# LIA.net
KiCad netlist of a schematic drawn in Altium Designer
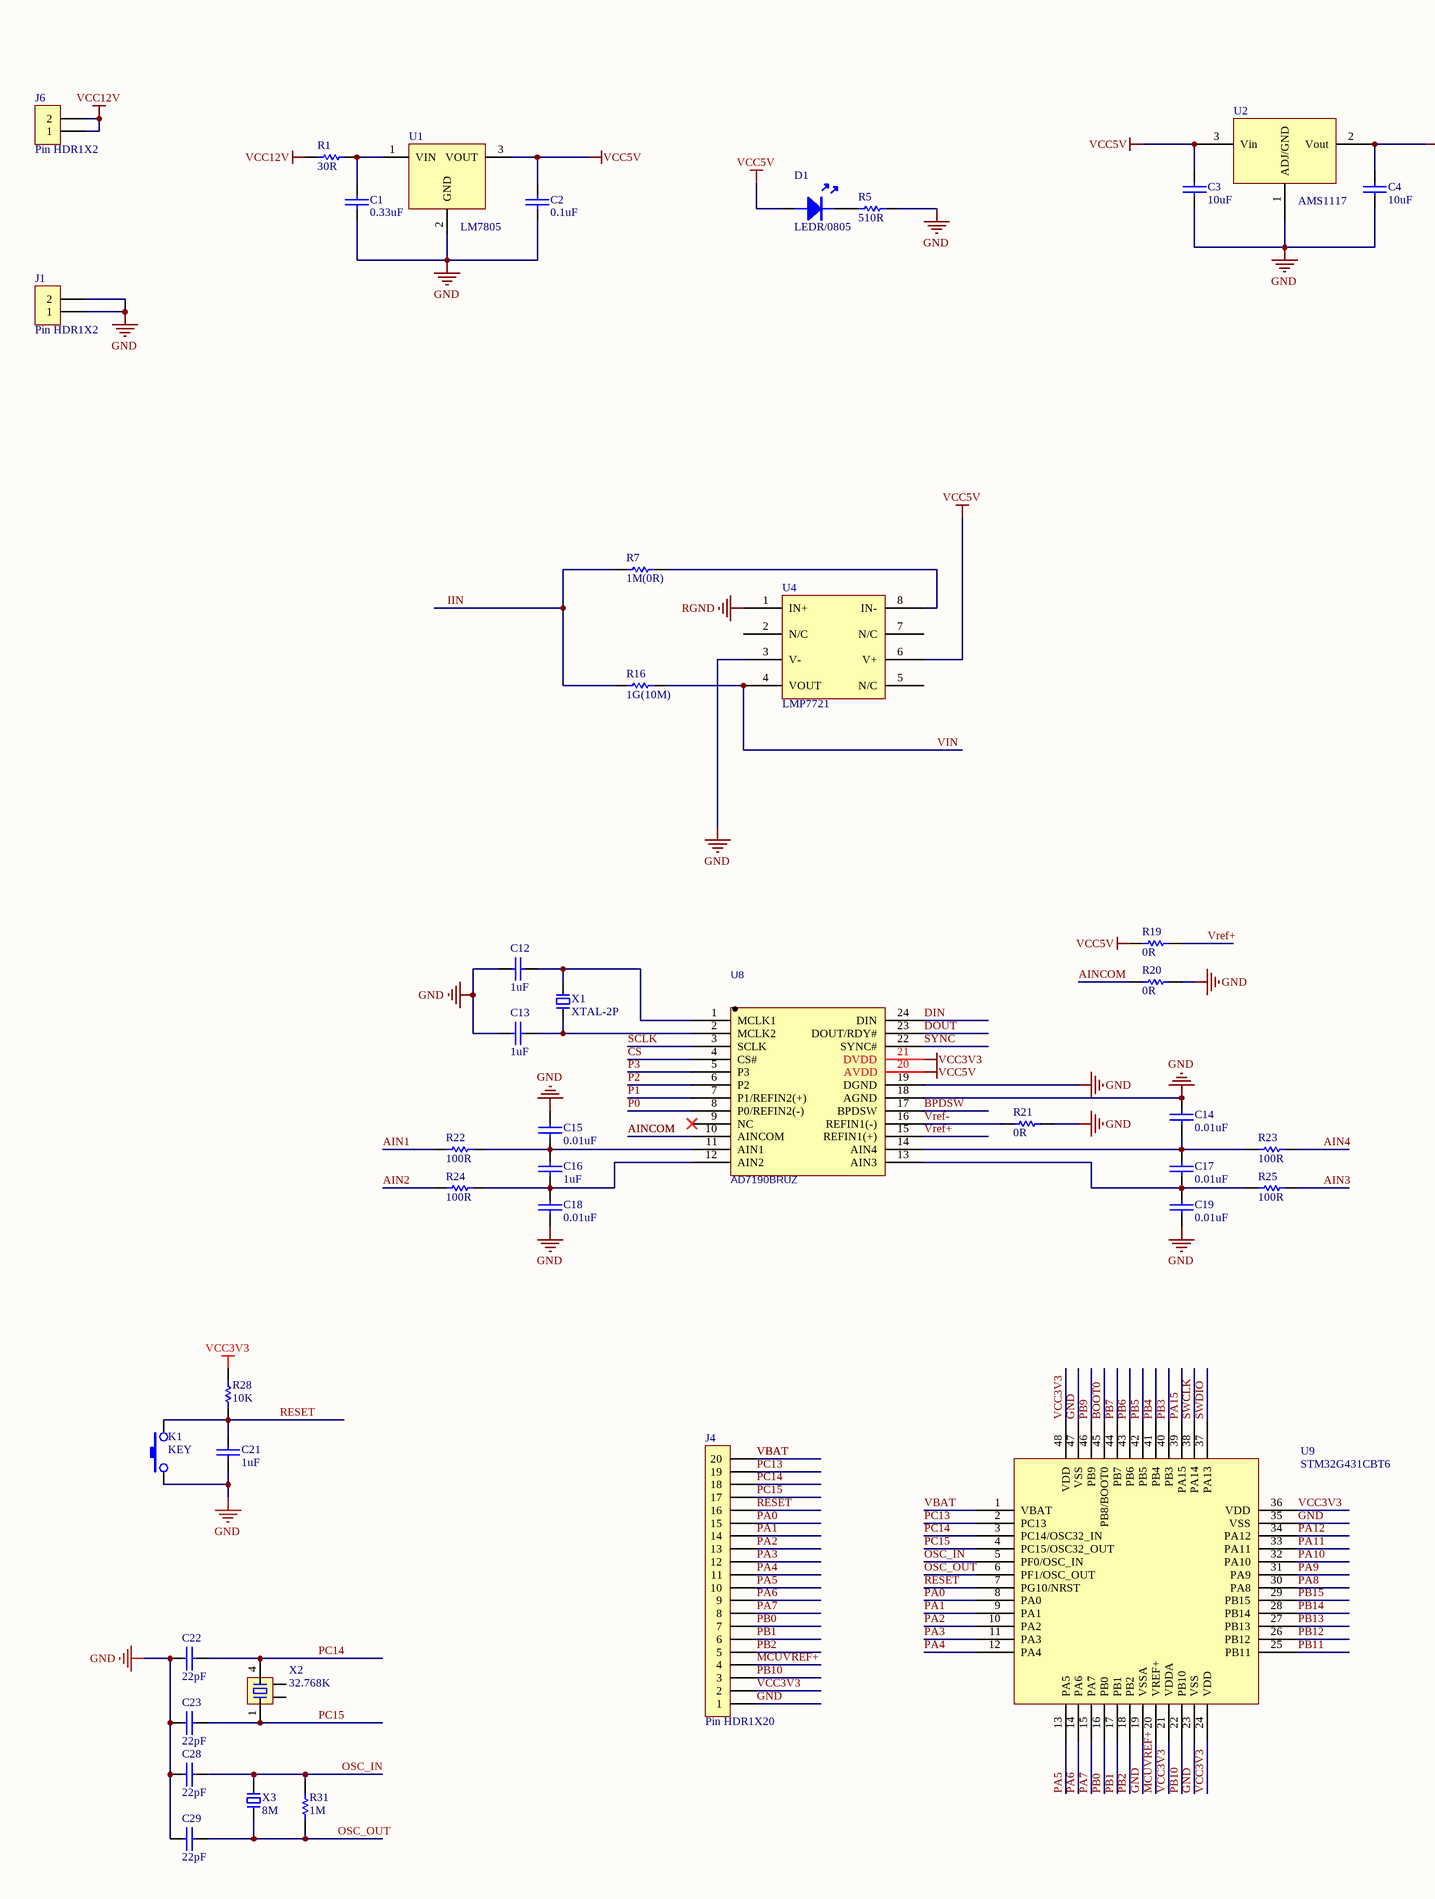
[diagram p0: LIA.SchDoc, left]
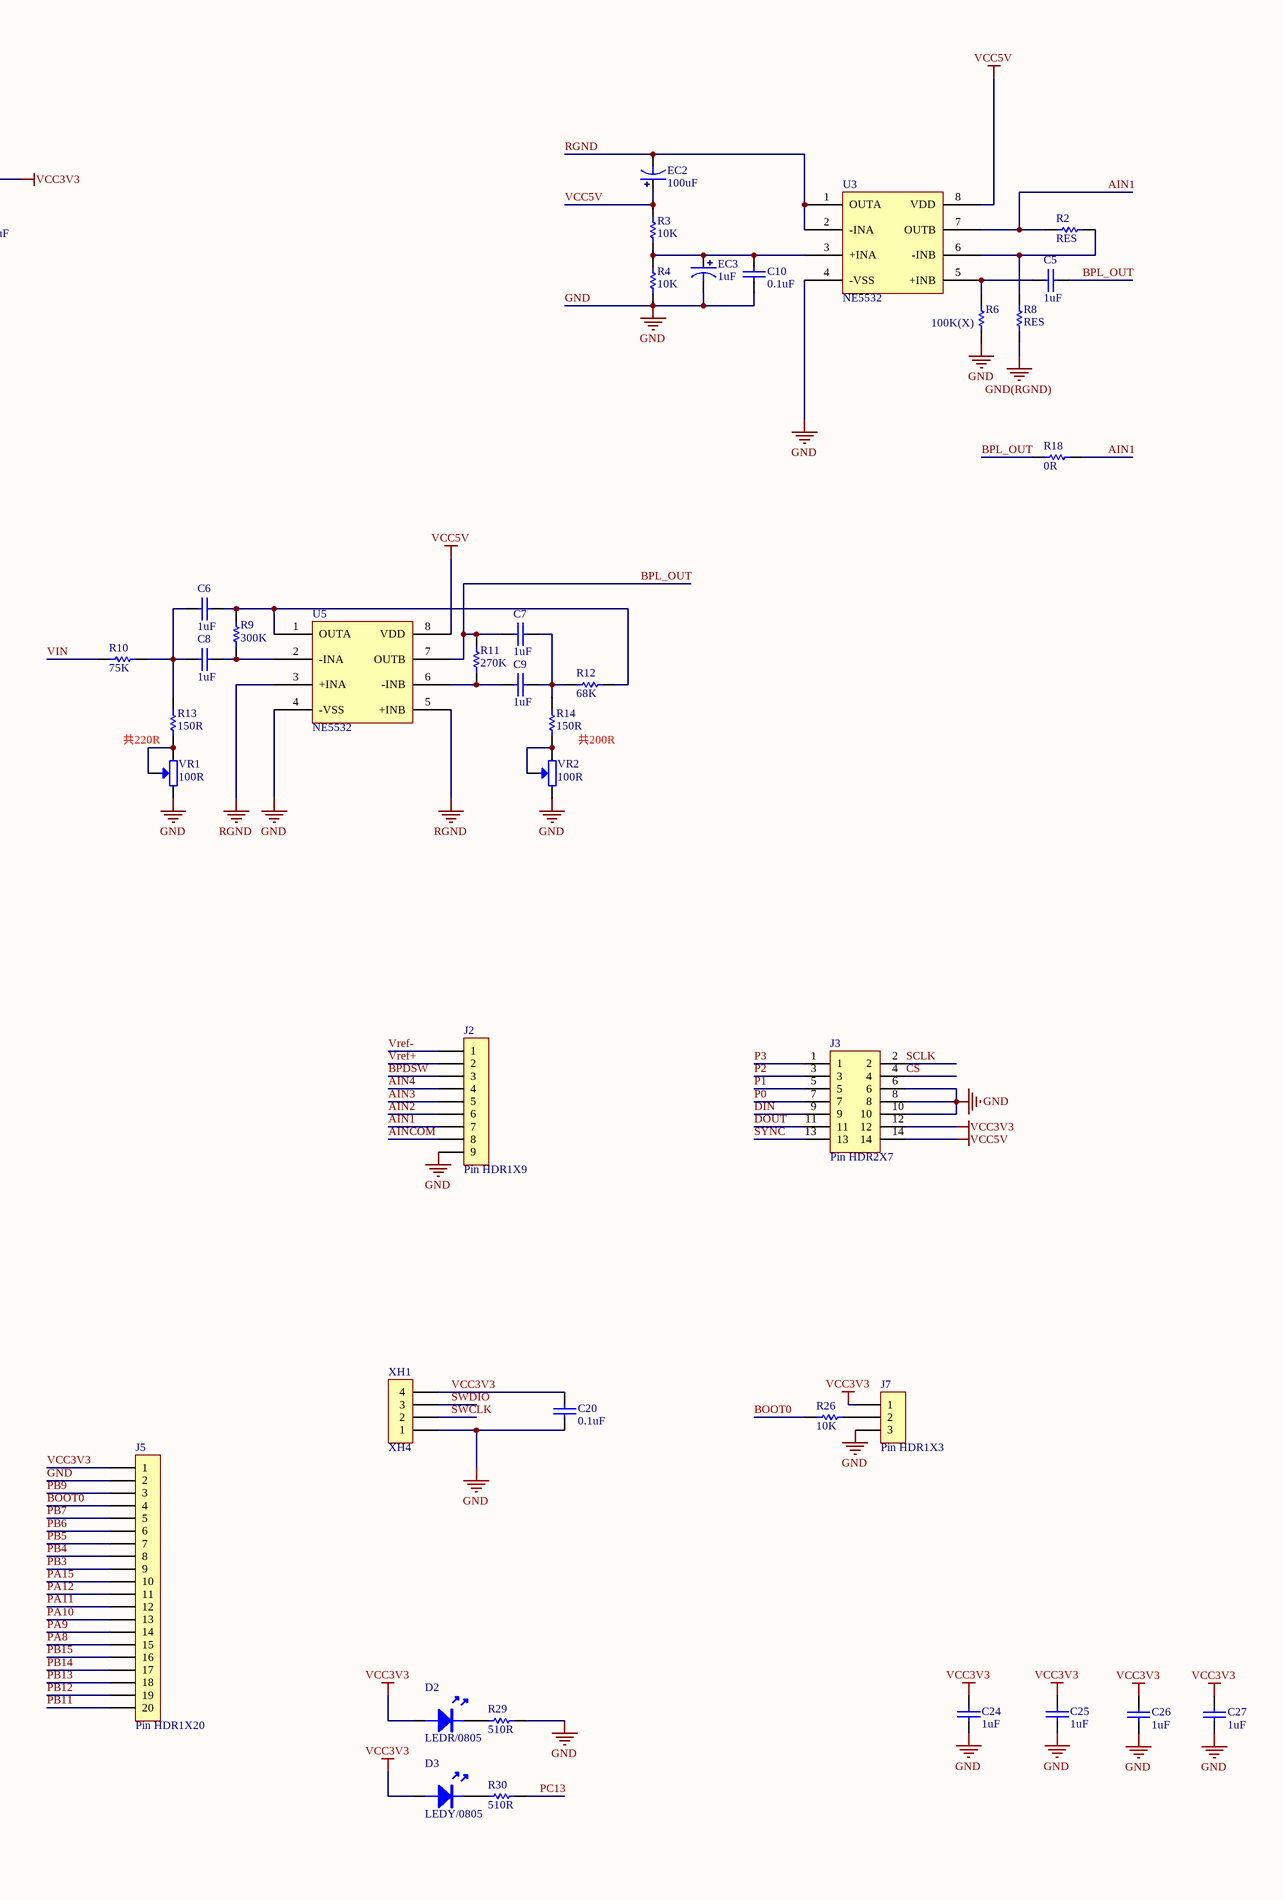
[diagram p1: LIA.SchDoc, right]

(export (version "E")
  (design (tool "Eeschema 10.0.6"))
  (components
    (comp (ref "C1")
      (value "0.33uF")
      (footprint "0603C")
      (description "无极性电容")
      (libsource (lib "电容") (part "CAP"))
    )
    (comp (ref "C2")
      (value "0.1uF")
      (footprint "0603C")
      (description "无极性电容")
      (libsource (lib "电容") (part "CAP"))
    )
    (comp (ref "C3")
      (value "10uF")
      (footprint "0603C")
      (description "无极性电容")
      (libsource (lib "电容") (part "CAP"))
    )
    (comp (ref "C4")
      (value "10uF")
      (footprint "0603C")
      (description "无极性电容")
      (libsource (lib "电容") (part "CAP"))
    )
    (comp (ref "C5")
      (value "1uF")
      (footprint "0603C")
      (description "无极性电容")
      (libsource (lib "电容") (part "CAP"))
    )
    (comp (ref "C6")
      (value "1uF")
      (footprint "DIP-7")
      (description "无极性电容")
      (libsource (lib "电容") (part "CAP"))
    )
    (comp (ref "C7")
      (value "1uF")
      (footprint "DIP-7")
      (description "无极性电容")
      (libsource (lib "电容") (part "CAP"))
    )
    (comp (ref "C8")
      (value "1uF")
      (footprint "DIP-7")
      (description "无极性电容")
      (libsource (lib "电容") (part "CAP"))
    )
    (comp (ref "C9")
      (value "1uF")
      (footprint "DIP-7")
      (description "无极性电容")
      (libsource (lib "电容") (part "CAP"))
    )
    (comp (ref "C10")
      (value "0.1uF")
      (footprint "0603C")
      (description "无极性电容")
      (libsource (lib "电容") (part "CAP"))
    )
    (comp (ref "C12")
      (value "1uF")
      (footprint "0603C")
      (description "无极性电容")
      (libsource (lib "电容") (part "CAP"))
    )
    (comp (ref "C13")
      (value "1uF")
      (footprint "0603C")
      (description "无极性电容")
      (libsource (lib "电容") (part "CAP"))
    )
    (comp (ref "C14")
      (value "0.01uF")
      (footprint "0603C")
      (description "无极性电容")
      (libsource (lib "电容") (part "CAP"))
    )
    (comp (ref "C15")
      (value "0.01uF")
      (footprint "0603C")
      (description "无极性电容")
      (libsource (lib "电容") (part "CAP"))
    )
    (comp (ref "C16")
      (value "1uF")
      (footprint "0603C")
      (description "无极性电容")
      (libsource (lib "电容") (part "CAP"))
    )
    (comp (ref "C17")
      (value "0.01uF")
      (footprint "0603C")
      (description "无极性电容")
      (libsource (lib "电容") (part "CAP"))
    )
    (comp (ref "C18")
      (value "0.01uF")
      (footprint "0603C")
      (description "无极性电容")
      (libsource (lib "电容") (part "CAP"))
    )
    (comp (ref "C19")
      (value "0.01uF")
      (footprint "0603C")
      (description "无极性电容")
      (libsource (lib "电容") (part "CAP"))
    )
    (comp (ref "C20")
      (value "0.1uF")
      (footprint "0603C")
      (description "无极性电容")
      (libsource (lib "电容") (part "CAP"))
    )
    (comp (ref "C21")
      (value "1uF")
      (footprint "0603C")
      (description "无极性电容")
      (libsource (lib "电容") (part "CAP"))
    )
    (comp (ref "C22")
      (value "22pF")
      (footprint "0603C")
      (description "无极性电容")
      (libsource (lib "电容") (part "CAP"))
    )
    (comp (ref "C23")
      (value "22pF")
      (footprint "0603C")
      (description "无极性电容")
      (libsource (lib "电容") (part "CAP"))
    )
    (comp (ref "C24")
      (value "1uF")
      (footprint "0603C")
      (description "无极性电容")
      (libsource (lib "电容") (part "CAP"))
    )
    (comp (ref "C25")
      (value "1uF")
      (footprint "0603C")
      (description "无极性电容")
      (libsource (lib "电容") (part "CAP"))
    )
    (comp (ref "C26")
      (value "1uF")
      (footprint "0603C")
      (description "无极性电容")
      (libsource (lib "电容") (part "CAP"))
    )
    (comp (ref "C27")
      (value "1uF")
      (footprint "0603C")
      (description "无极性电容")
      (libsource (lib "电容") (part "CAP"))
    )
    (comp (ref "C28")
      (value "22pF")
      (footprint "0603C")
      (description "无极性电容")
      (libsource (lib "电容") (part "CAP"))
    )
    (comp (ref "C29")
      (value "22pF")
      (footprint "0603C")
      (description "无极性电容")
      (libsource (lib "电容") (part "CAP"))
    )
    (comp (ref "D1") (value "LEDR/0805") (footprint "LED-0805R") (libsource (lib "LED") (part "LED")))
    (comp (ref "D2") (value "LEDR/0805") (footprint "LED-0805R") (libsource (lib "LED") (part "LED")))
    (comp (ref "D3") (value "LEDY/0805") (footprint "LED-0805Y") (libsource (lib "LED") (part "LED")))
    (comp (ref "EC2")
      (value "100uF")
      (footprint "SMD-EC6.3X6.3X10")
      (description "贴片电解电容")
      (libsource (lib "电容") (part "SMD_ECAP"))
    )
    (comp (ref "EC3")
      (value "1uF")
      (footprint "SMD-EC4.0X4.3X5.4")
      (description "贴片电解电容")
      (libsource (lib "电容") (part "SMD_ECAP"))
    )
    (comp (ref "J1")
      (value "Pin HDR1X2")
      (footprint "Pin HDR1X2/2.54mm-S")
      (libsource (lib "排针") (part "Pin HDR1X2"))
    )
    (comp (ref "J2")
      (value "Pin HDR1X9")
      (footprint "Pin HDR1X9/2.54mm-S")
      (libsource (lib "排针") (part "Pin HDR1X9"))
    )
    (comp (ref "J3")
      (value "Pin HDR2X7")
      (footprint "Pin HDR2X7/2.54mm-S")
      (libsource (lib "排针") (part "Pin HDR2X7"))
    )
    (comp (ref "J4")
      (value "Pin HDR1X20")
      (footprint "Pin HDR1X20/2.54mm-S")
      (libsource (lib "排针") (part "Pin HDR1X20"))
    )
    (comp (ref "J5")
      (value "Pin HDR1X20")
      (footprint "Pin HDR1X20/2.54mm-S")
      (libsource (lib "") (part "Pin HDR1X20_1"))
    )
    (comp (ref "J6")
      (value "Pin HDR1X2")
      (footprint "Pin HDR1X2/2.54mm-S")
      (libsource (lib "排针") (part "Pin HDR1X2"))
    )
    (comp (ref "J7")
      (value "Pin HDR1X3")
      (footprint "Pin HDR1X3/2.54mm-S")
      (libsource (lib "排针") (part "Pin HDR1X3"))
    )
    (comp (ref "K1") (value "KEY") (footprint "SMD-3X6X2.5") (libsource (lib "轻触开关") (part "KEY")))
    (comp (ref "R1") (value "30R") (footprint "0603R") (libsource (lib "电阻") (part "RES")))
    (comp (ref "R2") (value "RES") (footprint "0603R") (libsource (lib "电阻") (part "RES")))
    (comp (ref "R3") (value "10K") (footprint "0603R") (libsource (lib "电阻") (part "RES")))
    (comp (ref "R4") (value "10K") (footprint "0603R") (libsource (lib "电阻") (part "RES")))
    (comp (ref "R5") (value "510R") (footprint "0603R") (libsource (lib "电阻") (part "RES")))
    (comp (ref "R6") (value "100K(X)") (footprint "0603R") (libsource (lib "电阻") (part "RES")))
    (comp (ref "R7") (value "1M(0R)") (footprint "0603R") (libsource (lib "电阻") (part "RES")))
    (comp (ref "R8") (value "RES") (footprint "0603R") (libsource (lib "电阻") (part "RES")))
    (comp (ref "R9") (value "300K") (footprint "0603R") (libsource (lib "电阻") (part "RES")))
    (comp (ref "R10") (value "75K") (footprint "0603R") (libsource (lib "电阻") (part "RES")))
    (comp (ref "R11") (value "270K") (footprint "0603R") (libsource (lib "电阻") (part "RES")))
    (comp (ref "R12") (value "68K") (footprint "0603R") (libsource (lib "电阻") (part "RES")))
    (comp (ref "R13") (value "150R") (footprint "0603R") (libsource (lib "电阻") (part "RES")))
    (comp (ref "R14") (value "150R") (footprint "0603R") (libsource (lib "电阻") (part "RES")))
    (comp (ref "R16") (value "1G(10M)") (footprint "LONG") (libsource (lib "电阻") (part "RES")))
    (comp (ref "R18") (value "0R") (footprint "0603R") (libsource (lib "电阻") (part "RES")))
    (comp (ref "R19") (value "0R") (footprint "0603R") (libsource (lib "电阻") (part "RES")))
    (comp (ref "R20") (value "0R") (footprint "0603R") (libsource (lib "电阻") (part "RES")))
    (comp (ref "R21") (value "0R") (footprint "0603R") (libsource (lib "电阻") (part "RES")))
    (comp (ref "R22") (value "100R") (footprint "0603R") (libsource (lib "电阻") (part "RES")))
    (comp (ref "R23") (value "100R") (footprint "0603R") (libsource (lib "电阻") (part "RES")))
    (comp (ref "R24") (value "100R") (footprint "0603R") (libsource (lib "电阻") (part "RES")))
    (comp (ref "R25") (value "100R") (footprint "0603R") (libsource (lib "电阻") (part "RES")))
    (comp (ref "R26") (value "10K") (footprint "0603R") (libsource (lib "电阻") (part "RES")))
    (comp (ref "R28") (value "10K") (footprint "0603R") (libsource (lib "电阻") (part "RES")))
    (comp (ref "R29") (value "510R") (footprint "0603R") (libsource (lib "电阻") (part "RES")))
    (comp (ref "R30") (value "510R") (footprint "0603R") (libsource (lib "电阻") (part "RES")))
    (comp (ref "R31") (value "1M") (footprint "0603R") (libsource (lib "电阻") (part "RES")))
    (comp (ref "U1") (value "LM7805") (footprint "TO252") (libsource (lib "电源芯片") (part "LM7805")))
    (comp (ref "U2")
      (value "AMS1117")
      (footprint "SOT223")
      (description "三端稳压芯片")
      (libsource (lib "电源芯片") (part "AMS1117"))
    )
    (comp (ref "U3") (value "NE5532") (footprint "SOP8") (libsource (lib "未分类IC") (part "NE5532")))
    (comp (ref "U4") (value "LMP7721") (footprint "SOIC-8") (libsource (lib "未分类IC") (part "LMP7721")))
    (comp (ref "U5") (value "NE5532") (footprint "SOP8") (libsource (lib "未分类IC") (part "NE5532")))
    (comp (ref "U8")
      (value "AD7190BRUZ")
      (footprint "TSSOP24")
      (fields (field (name "BOM_SUPPLIER PART") "C578396") (field (name "CONTRIBUTOR") "LCSC"))
      (libsource (lib "未分类IC") (part "AD7190BRUZ"))
    )
    (comp (ref "U9")
      (value "STM32G431CBT6")
      (footprint "LQFP48 7X7")
      (libsource (lib "STM32系列") (part "STM32G431CBT6"))
    )
    (comp (ref "VR1") (value "100R") (footprint "3296W") (libsource (lib "电阻") (part "RESVR")))
    (comp (ref "VR2") (value "100R") (footprint "3296W") (libsource (lib "电阻") (part "RESVR")))
    (comp (ref "X1")
      (value "XTAL-2P")
      (footprint "OSC HC-49S")
      (description "2脚无源脚晶振")
      (libsource (lib "晶振") (part "XTAL-2P"))
    )
    (comp (ref "X2")
      (value "32.768K")
      (footprint "OSC MC-306")
      (description "MC系列4脚晶振")
      (libsource (lib "晶振") (part "XTAL-MC-4P"))
    )
    (comp (ref "X3")
      (value "8M")
      (footprint "OSC HC-49S")
      (description "2脚无源脚晶振")
      (libsource (lib "晶振") (part "XTAL-2P"))
    )
    (comp (ref "XH1") (value "XH4") (footprint "XH4/2.54mm/180") (libsource (lib "XH，VH") (part "XH4")))
  )
  (nets
    (net (code "1") (name "/AIN1") (class "Default")
      (node (ref "J2") (pin "7") (pinfunction "7_7") (pintype "passive"))
      (node (ref "R18") (pin "2") (pinfunction "2_2") (pintype "passive"))
      (node (ref "R2") (pin "1") (pinfunction "1_1") (pintype "passive"))
      (node (ref "R22") (pin "1") (pinfunction "1_1") (pintype "passive"))
      (node (ref "U3") (pin "7") (pinfunction "OUTB_7") (pintype "passive"))
    )
    (net (code "2") (name "/AIN2") (class "Default")
      (node (ref "J2") (pin "6") (pinfunction "6_6") (pintype "passive"))
      (node (ref "R24") (pin "1") (pinfunction "1_1") (pintype "passive"))
    )
    (net (code "3") (name "/AIN3") (class "Default")
      (node (ref "J2") (pin "5") (pinfunction "5_5") (pintype "passive"))
      (node (ref "R25") (pin "2") (pinfunction "2_2") (pintype "passive"))
    )
    (net (code "4") (name "/AIN4") (class "Default")
      (node (ref "J2") (pin "4") (pinfunction "4_4") (pintype "passive"))
      (node (ref "R23") (pin "2") (pinfunction "2_2") (pintype "passive"))
    )
    (net (code "5") (name "/AINCOM") (class "Default")
      (node (ref "J2") (pin "8") (pinfunction "8_8") (pintype "passive"))
      (node (ref "R20") (pin "1") (pinfunction "1_1") (pintype "passive"))
      (node (ref "U8") (pin "10") (pinfunction "AINCOM_10") (pintype "passive"))
    )
    (net (code "6") (name "/BOOT0") (class "Default")
      (node (ref "J5") (pin "4") (pinfunction "4_4") (pintype "passive"))
      (node (ref "R26") (pin "1") (pinfunction "1_1") (pintype "passive"))
      (node (ref "U9") (pin "45") (pinfunction "PB8/BOOT0_45") (pintype "passive"))
    )
    (net (code "7") (name "/BPDSW") (class "Default")
      (node (ref "J2") (pin "3") (pinfunction "3_3") (pintype "passive"))
      (node (ref "U8") (pin "17") (pinfunction "BPDSW_17") (pintype "passive"))
    )
    (net (code "8") (name "/BPL_OUT") (class "Default")
      (node (ref "C5") (pin "2") (pinfunction "2_2") (pintype "passive"))
      (node (ref "C7") (pin "2") (pinfunction "2_2") (pintype "passive"))
      (node (ref "R11") (pin "2") (pinfunction "2_2") (pintype "passive"))
      (node (ref "R18") (pin "1") (pinfunction "1_1") (pintype "passive"))
      (node (ref "U5") (pin "7") (pinfunction "OUTB_7") (pintype "passive"))
    )
    (net (code "9") (name "/CS") (class "Default")
      (node (ref "J3") (pin "4") (pinfunction "4_4") (pintype "passive"))
      (node (ref "U8") (pin "4") (pinfunction "CS#_4") (pintype "passive"))
    )
    (net (code "10") (name "/DIN") (class "Default")
      (node (ref "J3") (pin "9") (pinfunction "9_9") (pintype "passive"))
      (node (ref "U8") (pin "24") (pinfunction "DIN_24") (pintype "passive"))
    )
    (net (code "11") (name "/DOUT") (class "Default")
      (node (ref "J3") (pin "11") (pinfunction "11_11") (pintype "passive"))
      (node (ref "U8") (pin "23") (pinfunction "DOUT/RDY#_23") (pintype "passive"))
    )
    (net (code "12") (name "/IIN") (class "Default")
      (node (ref "R16") (pin "1") (pinfunction "1_1") (pintype "passive"))
      (node (ref "R7") (pin "2") (pinfunction "2_2") (pintype "passive"))
    )
    (net (code "13") (name "/MCUVREF+") (class "Default")
      (node (ref "J4") (pin "4") (pinfunction "4_4") (pintype "passive"))
      (node (ref "U9") (pin "20") (pinfunction "VREF+_20") (pintype "passive"))
    )
    (net (code "14") (name "/OSC_IN") (class "Default")
      (node (ref "C28") (pin "1") (pinfunction "1_1") (pintype "passive"))
      (node (ref "R31") (pin "2") (pinfunction "2_2") (pintype "passive"))
      (node (ref "U9") (pin "5") (pinfunction "PF0/OSC_IN_5") (pintype "passive"))
      (node (ref "X3") (pin "2") (pinfunction "2_2") (pintype "passive"))
    )
    (net (code "15") (name "/OSC_OUT") (class "Default")
      (node (ref "C29") (pin "1") (pinfunction "1_1") (pintype "passive"))
      (node (ref "R31") (pin "1") (pinfunction "1_1") (pintype "passive"))
      (node (ref "U9") (pin "6") (pinfunction "PF1/OSC_OUT_6") (pintype "passive"))
      (node (ref "X3") (pin "1") (pinfunction "1_1") (pintype "passive"))
    )
    (net (code "16") (name "/P0") (class "Default")
      (node (ref "J3") (pin "7") (pinfunction "7_7") (pintype "passive"))
      (node (ref "U8") (pin "8") (pinfunction "P0/REFIN2(-)_8") (pintype "passive"))
    )
    (net (code "17") (name "/P1") (class "Default")
      (node (ref "J3") (pin "5") (pinfunction "5_5") (pintype "passive"))
      (node (ref "U8") (pin "7") (pinfunction "P1/REFIN2(+)_7") (pintype "passive"))
    )
    (net (code "18") (name "/P2") (class "Default")
      (node (ref "J3") (pin "3") (pinfunction "3_3") (pintype "passive"))
      (node (ref "U8") (pin "6") (pinfunction "P2_6") (pintype "passive"))
    )
    (net (code "19") (name "/P3") (class "Default")
      (node (ref "J3") (pin "1") (pinfunction "1_1") (pintype "passive"))
      (node (ref "U8") (pin "5") (pinfunction "P3_5") (pintype "passive"))
    )
    (net (code "20") (name "/PA0") (class "Default")
      (node (ref "J4") (pin "15") (pinfunction "15_15") (pintype "passive"))
      (node (ref "U9") (pin "8") (pinfunction "PA0_8") (pintype "passive"))
    )
    (net (code "21") (name "/PA1") (class "Default")
      (node (ref "J4") (pin "14") (pinfunction "14_14") (pintype "passive"))
      (node (ref "U9") (pin "9") (pinfunction "PA1_9") (pintype "passive"))
    )
    (net (code "22") (name "/PA2") (class "Default")
      (node (ref "J4") (pin "13") (pinfunction "13_13") (pintype "passive"))
      (node (ref "U9") (pin "10") (pinfunction "PA2_10") (pintype "passive"))
    )
    (net (code "23") (name "/PA3") (class "Default")
      (node (ref "J4") (pin "12") (pinfunction "12_12") (pintype "passive"))
      (node (ref "U9") (pin "11") (pinfunction "PA3_11") (pintype "passive"))
    )
    (net (code "24") (name "/PA4") (class "Default")
      (node (ref "J4") (pin "11") (pinfunction "11_11") (pintype "passive"))
      (node (ref "U9") (pin "12") (pinfunction "PA4_12") (pintype "passive"))
    )
    (net (code "25") (name "/PA5") (class "Default")
      (node (ref "J4") (pin "10") (pinfunction "10_10") (pintype "passive"))
      (node (ref "U9") (pin "13") (pinfunction "PA5_13") (pintype "passive"))
    )
    (net (code "26") (name "/PA6") (class "Default")
      (node (ref "J4") (pin "9") (pinfunction "9_9") (pintype "passive"))
      (node (ref "U9") (pin "14") (pinfunction "PA6_14") (pintype "passive"))
    )
    (net (code "27") (name "/PA7") (class "Default")
      (node (ref "J4") (pin "8") (pinfunction "8_8") (pintype "passive"))
      (node (ref "U9") (pin "15") (pinfunction "PA7_15") (pintype "passive"))
    )
    (net (code "28") (name "/PA8") (class "Default")
      (node (ref "J5") (pin "15") (pinfunction "15_15") (pintype "passive"))
      (node (ref "U9") (pin "30") (pinfunction "PA8_30") (pintype "passive"))
    )
    (net (code "29") (name "/PA9") (class "Default")
      (node (ref "J5") (pin "14") (pinfunction "14_14") (pintype "passive"))
      (node (ref "U9") (pin "31") (pinfunction "PA9_31") (pintype "passive"))
    )
    (net (code "30") (name "/PA10") (class "Default")
      (node (ref "J5") (pin "13") (pinfunction "13_13") (pintype "passive"))
      (node (ref "U9") (pin "32") (pinfunction "PA10_32") (pintype "passive"))
    )
    (net (code "31") (name "/PA11") (class "Default")
      (node (ref "J5") (pin "12") (pinfunction "12_12") (pintype "passive"))
      (node (ref "U9") (pin "33") (pinfunction "PA11_33") (pintype "passive"))
    )
    (net (code "32") (name "/PA12") (class "Default")
      (node (ref "J5") (pin "11") (pinfunction "11_11") (pintype "passive"))
      (node (ref "U9") (pin "34") (pinfunction "PA12_34") (pintype "passive"))
    )
    (net (code "33") (name "/PA15") (class "Default")
      (node (ref "J5") (pin "10") (pinfunction "10_10") (pintype "passive"))
      (node (ref "U9") (pin "39") (pinfunction "PA15_39") (pintype "passive"))
    )
    (net (code "34") (name "/PB0") (class "Default")
      (node (ref "J4") (pin "7") (pinfunction "7_7") (pintype "passive"))
      (node (ref "U9") (pin "16") (pinfunction "PB0_16") (pintype "passive"))
    )
    (net (code "35") (name "/PB1") (class "Default")
      (node (ref "J4") (pin "6") (pinfunction "6_6") (pintype "passive"))
      (node (ref "U9") (pin "17") (pinfunction "PB1_17") (pintype "passive"))
    )
    (net (code "36") (name "/PB2") (class "Default")
      (node (ref "J4") (pin "5") (pinfunction "5_5") (pintype "passive"))
      (node (ref "U9") (pin "18") (pinfunction "PB2_18") (pintype "passive"))
    )
    (net (code "37") (name "/PB3") (class "Default")
      (node (ref "J5") (pin "9") (pinfunction "9_9") (pintype "passive"))
      (node (ref "U9") (pin "40") (pinfunction "PB3_40") (pintype "passive"))
    )
    (net (code "38") (name "/PB4") (class "Default")
      (node (ref "J5") (pin "8") (pinfunction "8_8") (pintype "passive"))
      (node (ref "U9") (pin "41") (pinfunction "PB4_41") (pintype "passive"))
    )
    (net (code "39") (name "/PB5") (class "Default")
      (node (ref "J5") (pin "7") (pinfunction "7_7") (pintype "passive"))
      (node (ref "U9") (pin "42") (pinfunction "PB5_42") (pintype "passive"))
    )
    (net (code "40") (name "/PB6") (class "Default")
      (node (ref "J5") (pin "6") (pinfunction "6_6") (pintype "passive"))
      (node (ref "U9") (pin "43") (pinfunction "PB6_43") (pintype "passive"))
    )
    (net (code "41") (name "/PB7") (class "Default")
      (node (ref "J5") (pin "5") (pinfunction "5_5") (pintype "passive"))
      (node (ref "U9") (pin "44") (pinfunction "PB7_44") (pintype "passive"))
    )
    (net (code "42") (name "/PB9") (class "Default")
      (node (ref "J5") (pin "3") (pinfunction "3_3") (pintype "passive"))
      (node (ref "U9") (pin "46") (pinfunction "PB9_46") (pintype "passive"))
    )
    (net (code "43") (name "/PB10") (class "Default")
      (node (ref "J4") (pin "3") (pinfunction "3_3") (pintype "passive"))
      (node (ref "U9") (pin "22") (pinfunction "PB10_22") (pintype "passive"))
    )
    (net (code "44") (name "/PB11") (class "Default")
      (node (ref "J5") (pin "20") (pinfunction "20_20") (pintype "passive"))
      (node (ref "U9") (pin "25") (pinfunction "PB11_25") (pintype "passive"))
    )
    (net (code "45") (name "/PB12") (class "Default")
      (node (ref "J5") (pin "19") (pinfunction "19_19") (pintype "passive"))
      (node (ref "U9") (pin "26") (pinfunction "PB12_26") (pintype "passive"))
    )
    (net (code "46") (name "/PB13") (class "Default")
      (node (ref "J5") (pin "18") (pinfunction "18_18") (pintype "passive"))
      (node (ref "U9") (pin "27") (pinfunction "PB13_27") (pintype "passive"))
    )
    (net (code "47") (name "/PB14") (class "Default")
      (node (ref "J5") (pin "17") (pinfunction "17_17") (pintype "passive"))
      (node (ref "U9") (pin "28") (pinfunction "PB14_28") (pintype "passive"))
    )
    (net (code "48") (name "/PB15") (class "Default")
      (node (ref "J5") (pin "16") (pinfunction "16_16") (pintype "passive"))
      (node (ref "U9") (pin "29") (pinfunction "PB15_29") (pintype "passive"))
    )
    (net (code "49") (name "/PC13") (class "Default")
      (node (ref "J4") (pin "19") (pinfunction "19_19") (pintype "passive"))
      (node (ref "R30") (pin "2") (pinfunction "2_2") (pintype "passive"))
      (node (ref "U9") (pin "2") (pinfunction "PC13_2") (pintype "passive"))
    )
    (net (code "50") (name "/PC14") (class "Default")
      (node (ref "C22") (pin "1") (pinfunction "1_1") (pintype "passive"))
      (node (ref "J4") (pin "18") (pinfunction "18_18") (pintype "passive"))
      (node (ref "U9") (pin "3") (pinfunction "PC14/OSC32_IN_3") (pintype "passive"))
      (node (ref "X2") (pin "4") (pinfunction "4_4") (pintype "passive"))
    )
    (net (code "51") (name "/PC15") (class "Default")
      (node (ref "C23") (pin "1") (pinfunction "1_1") (pintype "passive"))
      (node (ref "J4") (pin "17") (pinfunction "17_17") (pintype "passive"))
      (node (ref "U9") (pin "4") (pinfunction "PC15/OSC32_OUT_4") (pintype "passive"))
      (node (ref "X2") (pin "1") (pinfunction "1_1") (pintype "passive"))
    )
    (net (code "52") (name "/RESET") (class "Default")
      (node (ref "C21") (pin "2") (pinfunction "2_2") (pintype "passive"))
      (node (ref "J4") (pin "16") (pinfunction "16_16") (pintype "passive"))
      (node (ref "K1") (pin "3") (pinfunction "3_3") (pintype "passive"))
      (node (ref "R28") (pin "2") (pinfunction "2_2") (pintype "passive"))
      (node (ref "U9") (pin "7") (pinfunction "PG10/NRST_7") (pintype "passive"))
    )
    (net (code "53") (name "/SCLK") (class "Default")
      (node (ref "J3") (pin "2") (pinfunction "2_2") (pintype "passive"))
      (node (ref "U8") (pin "3") (pinfunction "SCLK_3") (pintype "passive"))
    )
    (net (code "54") (name "/SWCLK") (class "Default")
      (node (ref "U9") (pin "38") (pinfunction "PA14_38") (pintype "passive"))
      (node (ref "XH1") (pin "2") (pinfunction "2_2") (pintype "passive"))
    )
    (net (code "55") (name "/SWDIO") (class "Default")
      (node (ref "U9") (pin "37") (pinfunction "PA13_37") (pintype "passive"))
      (node (ref "XH1") (pin "3") (pinfunction "3_3") (pintype "passive"))
    )
    (net (code "56") (name "/SYNC") (class "Default")
      (node (ref "J3") (pin "13") (pinfunction "13_13") (pintype "passive"))
      (node (ref "U8") (pin "22") (pinfunction "SYNC#_22") (pintype "passive"))
    )
    (net (code "57") (name "/VBAT") (class "Default")
      (node (ref "J4") (pin "20") (pinfunction "20_20") (pintype "passive"))
      (node (ref "U9") (pin "1") (pinfunction "VBAT_1") (pintype "passive"))
    )
    (net (code "58") (name "/VIN") (class "Default")
      (node (ref "R10") (pin "2") (pinfunction "2_2") (pintype "passive"))
      (node (ref "R16") (pin "2") (pinfunction "2_2") (pintype "passive"))
      (node (ref "U4") (pin "4") (pinfunction "VOUT_4") (pintype "passive"))
    )
    (net (code "59") (name "/Vref+") (class "Default")
      (node (ref "J2") (pin "2") (pinfunction "2_2") (pintype "passive"))
      (node (ref "R19") (pin "2") (pinfunction "2_2") (pintype "passive"))
      (node (ref "U8") (pin "15") (pinfunction "REFIN1(+)_15") (pintype "passive"))
    )
    (net (code "60") (name "/Vref-") (class "Default")
      (node (ref "J2") (pin "1") (pinfunction "1_1") (pintype "passive"))
      (node (ref "R21") (pin "1") (pinfunction "1_1") (pintype "passive"))
      (node (ref "U8") (pin "16") (pinfunction "REFIN1(-)_16") (pintype "passive"))
    )
    (net (code "61") (name "GND") (class "Default")
      (node (ref "C1") (pin "1") (pinfunction "1_1") (pintype "passive"))
      (node (ref "C10") (pin "1") (pinfunction "1_1") (pintype "passive"))
      (node (ref "C12") (pin "2") (pinfunction "2_2") (pintype "passive"))
      (node (ref "C13") (pin "2") (pinfunction "2_2") (pintype "passive"))
      (node (ref "C14") (pin "2") (pinfunction "2_2") (pintype "passive"))
      (node (ref "C15") (pin "2") (pinfunction "2_2") (pintype "passive"))
      (node (ref "C18") (pin "1") (pinfunction "1_1") (pintype "passive"))
      (node (ref "C19") (pin "1") (pinfunction "1_1") (pintype "passive"))
      (node (ref "C2") (pin "1") (pinfunction "1_1") (pintype "passive"))
      (node (ref "C20") (pin "1") (pinfunction "1_1") (pintype "passive"))
      (node (ref "C21") (pin "1") (pinfunction "1_1") (pintype "passive"))
      (node (ref "C22") (pin "2") (pinfunction "2_2") (pintype "passive"))
      (node (ref "C23") (pin "2") (pinfunction "2_2") (pintype "passive"))
      (node (ref "C24") (pin "1") (pinfunction "1_1") (pintype "passive"))
      (node (ref "C25") (pin "1") (pinfunction "1_1") (pintype "passive"))
      (node (ref "C26") (pin "1") (pinfunction "1_1") (pintype "passive"))
      (node (ref "C27") (pin "1") (pinfunction "1_1") (pintype "passive"))
      (node (ref "C28") (pin "2") (pinfunction "2_2") (pintype "passive"))
      (node (ref "C29") (pin "2") (pinfunction "2_2") (pintype "passive"))
      (node (ref "C3") (pin "1") (pinfunction "1_1") (pintype "passive"))
      (node (ref "C4") (pin "1") (pinfunction "1_1") (pintype "passive"))
      (node (ref "EC3") (pin "2") (pinfunction "2_2") (pintype "passive"))
      (node (ref "J1") (pin "1") (pinfunction "1_1") (pintype "passive"))
      (node (ref "J1") (pin "2") (pinfunction "2_2") (pintype "passive"))
      (node (ref "J2") (pin "9") (pinfunction "9_9") (pintype "passive"))
      (node (ref "J3") (pin "10") (pinfunction "10_10") (pintype "passive"))
      (node (ref "J3") (pin "6") (pinfunction "6_6") (pintype "passive"))
      (node (ref "J3") (pin "8") (pinfunction "8_8") (pintype "passive"))
      (node (ref "J4") (pin "1") (pinfunction "1_1") (pintype "passive"))
      (node (ref "J5") (pin "2") (pinfunction "2_2") (pintype "passive"))
      (node (ref "J7") (pin "3") (pinfunction "3_3") (pintype "passive"))
      (node (ref "K1") (pin "1") (pinfunction "1_1") (pintype "passive"))
      (node (ref "R20") (pin "2") (pinfunction "2_2") (pintype "passive"))
      (node (ref "R21") (pin "2") (pinfunction "2_2") (pintype "passive"))
      (node (ref "R29") (pin "2") (pinfunction "2_2") (pintype "passive"))
      (node (ref "R4") (pin "2") (pinfunction "2_2") (pintype "passive"))
      (node (ref "R5") (pin "2") (pinfunction "2_2") (pintype "passive"))
      (node (ref "R6") (pin "1") (pinfunction "1_1") (pintype "passive"))
      (node (ref "U1") (pin "2") (pinfunction "GND_2") (pintype "passive"))
      (node (ref "U2") (pin "1") (pinfunction "ADJ/GND_1") (pintype "passive"))
      (node (ref "U3") (pin "4") (pinfunction "-VSS_4") (pintype "passive"))
      (node (ref "U4") (pin "3") (pinfunction "V-_3") (pintype "passive"))
      (node (ref "U5") (pin "4") (pinfunction "-VSS_4") (pintype "passive"))
      (node (ref "U8") (pin "18") (pinfunction "AGND_18") (pintype "passive"))
      (node (ref "U8") (pin "19") (pinfunction "DGND_19") (pintype "passive"))
      (node (ref "U9") (pin "19") (pinfunction "VSSA_19") (pintype "passive"))
      (node (ref "U9") (pin "23") (pinfunction "VSS_23") (pintype "passive"))
      (node (ref "U9") (pin "35") (pinfunction "VSS_35") (pintype "passive"))
      (node (ref "U9") (pin "47") (pinfunction "VSS_47") (pintype "passive"))
      (node (ref "VR1") (pin "1") (pinfunction "1_1") (pintype "passive"))
      (node (ref "VR2") (pin "1") (pinfunction "1_1") (pintype "passive"))
      (node (ref "XH1") (pin "1") (pinfunction "1_1") (pintype "passive"))
    )
    (net (code "62") (name "GND(RGND)") (class "Default")
      (node (ref "R8") (pin "2") (pinfunction "2_2") (pintype "passive"))
    )
    (net (code "63") (name "Net-(C6-Pad2)") (class "Default")
      (node (ref "C6") (pin "2") (pinfunction "2_2") (pintype "passive"))
      (node (ref "C8") (pin "1") (pinfunction "1_1") (pintype "passive"))
      (node (ref "R10") (pin "1") (pinfunction "1_1") (pintype "passive"))
      (node (ref "R13") (pin "1") (pinfunction "1_1") (pintype "passive"))
    )
    (net (code "64") (name "Net-(C7-Pad1)") (class "Default")
      (node (ref "C7") (pin "1") (pinfunction "1_1") (pintype "passive"))
      (node (ref "C9") (pin "2") (pinfunction "2_2") (pintype "passive"))
      (node (ref "R12") (pin "2") (pinfunction "2_2") (pintype "passive"))
      (node (ref "R14") (pin "1") (pinfunction "1_1") (pintype "passive"))
    )
    (net (code "65") (name "Net-(D1-PadK)") (class "Default")
      (node (ref "D1") (pin "K") (pinfunction "K_K") (pintype "passive"))
      (node (ref "R5") (pin "1") (pinfunction "1_1") (pintype "passive"))
    )
    (net (code "66") (name "Net-(D2-PadK)") (class "Default")
      (node (ref "D2") (pin "K") (pinfunction "K_K") (pintype "passive"))
      (node (ref "R29") (pin "1") (pinfunction "1_1") (pintype "passive"))
    )
    (net (code "67") (name "Net-(D3-PadK)") (class "Default")
      (node (ref "D3") (pin "K") (pinfunction "K_K") (pintype "passive"))
      (node (ref "R30") (pin "1") (pinfunction "1_1") (pintype "passive"))
    )
    (net (code "68") (name "Net-(J7-Pad2)") (class "Default")
      (node (ref "J7") (pin "2") (pinfunction "2_2") (pintype "passive"))
      (node (ref "R26") (pin "2") (pinfunction "2_2") (pintype "passive"))
    )
    (net (code "69") (name "Net-(R13-Pad2)") (class "Default")
      (node (ref "R13") (pin "2") (pinfunction "2_2") (pintype "passive"))
      (node (ref "VR1") (pin "2") (pinfunction "2_2") (pintype "passive"))
    )
    (net (code "70") (name "Net-(R14-Pad2)") (class "Default")
      (node (ref "R14") (pin "2") (pinfunction "2_2") (pintype "passive"))
      (node (ref "VR2") (pin "2") (pinfunction "2_2") (pintype "passive"))
    )
    (net (code "71") (name "Net-(U1-VIN)") (class "Default")
      (node (ref "C1") (pin "2") (pinfunction "2_2") (pintype "passive"))
      (node (ref "R1") (pin "2") (pinfunction "2_2") (pintype "passive"))
      (node (ref "U1") (pin "1") (pinfunction "VIN_1") (pintype "passive"))
    )
    (net (code "72") (name "Net-(U3-+INA)") (class "Default")
      (node (ref "C10") (pin "2") (pinfunction "2_2") (pintype "passive"))
      (node (ref "EC3") (pin "1") (pinfunction "1_1") (pintype "passive"))
      (node (ref "R3") (pin "2") (pinfunction "2_2") (pintype "passive"))
      (node (ref "R4") (pin "1") (pinfunction "1_1") (pintype "passive"))
      (node (ref "U3") (pin "3") (pinfunction "+INA_3") (pintype "passive"))
    )
    (net (code "73") (name "Net-(U3-+INB)") (class "Default")
      (node (ref "C5") (pin "1") (pinfunction "1_1") (pintype "passive"))
      (node (ref "R6") (pin "2") (pinfunction "2_2") (pintype "passive"))
      (node (ref "U3") (pin "5") (pinfunction "+INB_5") (pintype "passive"))
    )
    (net (code "74") (name "Net-(U3--INB)") (class "Default")
      (node (ref "R2") (pin "2") (pinfunction "2_2") (pintype "passive"))
      (node (ref "R8") (pin "1") (pinfunction "1_1") (pintype "passive"))
      (node (ref "U3") (pin "6") (pinfunction "-INB_6") (pintype "passive"))
    )
    (net (code "75") (name "Net-(U4-IN-)") (class "Default")
      (node (ref "R7") (pin "1") (pinfunction "1_1") (pintype "passive"))
      (node (ref "U4") (pin "8") (pinfunction "IN-_8") (pintype "passive"))
    )
    (net (code "76") (name "Net-(U5--INA)") (class "Default")
      (node (ref "C8") (pin "2") (pinfunction "2_2") (pintype "passive"))
      (node (ref "R9") (pin "1") (pinfunction "1_1") (pintype "passive"))
      (node (ref "U5") (pin "2") (pinfunction "-INA_2") (pintype "passive"))
    )
    (net (code "77") (name "Net-(U5--INB)") (class "Default")
      (node (ref "C9") (pin "1") (pinfunction "1_1") (pintype "passive"))
      (node (ref "R11") (pin "1") (pinfunction "1_1") (pintype "passive"))
      (node (ref "U5") (pin "6") (pinfunction "-INB_6") (pintype "passive"))
    )
    (net (code "78") (name "Net-(U5-OUTA)") (class "Default")
      (node (ref "C6") (pin "1") (pinfunction "1_1") (pintype "passive"))
      (node (ref "R12") (pin "1") (pinfunction "1_1") (pintype "passive"))
      (node (ref "R9") (pin "2") (pinfunction "2_2") (pintype "passive"))
      (node (ref "U5") (pin "1") (pinfunction "OUTA_1") (pintype "passive"))
    )
    (net (code "79") (name "Net-(U8-AIN1)") (class "Default")
      (node (ref "C15") (pin "1") (pinfunction "1_1") (pintype "passive"))
      (node (ref "C16") (pin "2") (pinfunction "2_2") (pintype "passive"))
      (node (ref "R22") (pin "2") (pinfunction "2_2") (pintype "passive"))
      (node (ref "U8") (pin "11") (pinfunction "AIN1_11") (pintype "passive"))
    )
    (net (code "80") (name "Net-(U8-AIN2)") (class "Default")
      (node (ref "C16") (pin "1") (pinfunction "1_1") (pintype "passive"))
      (node (ref "C18") (pin "2") (pinfunction "2_2") (pintype "passive"))
      (node (ref "R24") (pin "2") (pinfunction "2_2") (pintype "passive"))
      (node (ref "U8") (pin "12") (pinfunction "AIN2_12") (pintype "passive"))
    )
    (net (code "81") (name "Net-(U8-AIN3)") (class "Default")
      (node (ref "C17") (pin "1") (pinfunction "1_1") (pintype "passive"))
      (node (ref "C19") (pin "2") (pinfunction "2_2") (pintype "passive"))
      (node (ref "R25") (pin "1") (pinfunction "1_1") (pintype "passive"))
      (node (ref "U8") (pin "13") (pinfunction "AIN3_13") (pintype "passive"))
    )
    (net (code "82") (name "Net-(U8-AIN4)") (class "Default")
      (node (ref "C14") (pin "1") (pinfunction "1_1") (pintype "passive"))
      (node (ref "C17") (pin "2") (pinfunction "2_2") (pintype "passive"))
      (node (ref "R23") (pin "1") (pinfunction "1_1") (pintype "passive"))
      (node (ref "U8") (pin "14") (pinfunction "AIN4_14") (pintype "passive"))
    )
    (net (code "83") (name "Net-(U8-MCLK1)") (class "Default")
      (node (ref "C12") (pin "1") (pinfunction "1_1") (pintype "passive"))
      (node (ref "U8") (pin "1") (pinfunction "MCLK1_1") (pintype "passive"))
      (node (ref "X1") (pin "2") (pinfunction "2_2") (pintype "passive"))
    )
    (net (code "84") (name "Net-(U8-MCLK2)") (class "Default")
      (node (ref "C13") (pin "1") (pinfunction "1_1") (pintype "passive"))
      (node (ref "U8") (pin "2") (pinfunction "MCLK2_2") (pintype "passive"))
      (node (ref "X1") (pin "1") (pinfunction "1_1") (pintype "passive"))
    )
    (net (code "85") (name "RGND") (class "Default")
      (node (ref "EC2") (pin "2") (pinfunction "2_2") (pintype "passive"))
      (node (ref "U3") (pin "1") (pinfunction "OUTA_1") (pintype "passive"))
      (node (ref "U3") (pin "2") (pinfunction "-INA_2") (pintype "passive"))
      (node (ref "U4") (pin "1") (pinfunction "IN+_1") (pintype "passive"))
      (node (ref "U5") (pin "3") (pinfunction "+INA_3") (pintype "passive"))
      (node (ref "U5") (pin "5") (pinfunction "+INB_5") (pintype "passive"))
    )
    (net (code "86") (name "VCC3V3") (class "Default")
      (node (ref "C20") (pin "2") (pinfunction "2_2") (pintype "passive"))
      (node (ref "C24") (pin "2") (pinfunction "2_2") (pintype "passive"))
      (node (ref "C25") (pin "2") (pinfunction "2_2") (pintype "passive"))
      (node (ref "C26") (pin "2") (pinfunction "2_2") (pintype "passive"))
      (node (ref "C27") (pin "2") (pinfunction "2_2") (pintype "passive"))
      (node (ref "C4") (pin "2") (pinfunction "2_2") (pintype "passive"))
      (node (ref "D2") (pin "A") (pinfunction "A_A") (pintype "passive"))
      (node (ref "D3") (pin "A") (pinfunction "A_A") (pintype "passive"))
      (node (ref "J3") (pin "12") (pinfunction "12_12") (pintype "passive"))
      (node (ref "J4") (pin "2") (pinfunction "2_2") (pintype "passive"))
      (node (ref "J5") (pin "1") (pinfunction "1_1") (pintype "passive"))
      (node (ref "J7") (pin "1") (pinfunction "1_1") (pintype "passive"))
      (node (ref "R28") (pin "1") (pinfunction "1_1") (pintype "passive"))
      (node (ref "U2") (pin "2") (pinfunction "Vout_2") (pintype "passive"))
      (node (ref "U8") (pin "21") (pinfunction "DVDD_21") (pintype "passive"))
      (node (ref "U9") (pin "21") (pinfunction "VDDA_21") (pintype "passive"))
      (node (ref "U9") (pin "24") (pinfunction "VDD_24") (pintype "passive"))
      (node (ref "U9") (pin "36") (pinfunction "VDD_36") (pintype "passive"))
      (node (ref "U9") (pin "48") (pinfunction "VDD_48") (pintype "passive"))
      (node (ref "XH1") (pin "4") (pinfunction "4_4") (pintype "passive"))
    )
    (net (code "87") (name "VCC5V") (class "Default")
      (node (ref "C2") (pin "2") (pinfunction "2_2") (pintype "passive"))
      (node (ref "C3") (pin "2") (pinfunction "2_2") (pintype "passive"))
      (node (ref "D1") (pin "A") (pinfunction "A_A") (pintype "passive"))
      (node (ref "EC2") (pin "1") (pinfunction "1_1") (pintype "passive"))
      (node (ref "J3") (pin "14") (pinfunction "14_14") (pintype "passive"))
      (node (ref "R19") (pin "1") (pinfunction "1_1") (pintype "passive"))
      (node (ref "R3") (pin "1") (pinfunction "1_1") (pintype "passive"))
      (node (ref "U1") (pin "3") (pinfunction "VOUT_3") (pintype "passive"))
      (node (ref "U2") (pin "3") (pinfunction "Vin_3") (pintype "passive"))
      (node (ref "U3") (pin "8") (pinfunction "VDD_8") (pintype "passive"))
      (node (ref "U4") (pin "6") (pinfunction "V+_6") (pintype "passive"))
      (node (ref "U5") (pin "8") (pinfunction "VDD_8") (pintype "passive"))
      (node (ref "U8") (pin "20") (pinfunction "AVDD_20") (pintype "passive"))
    )
    (net (code "88") (name "VCC12V") (class "Default")
      (node (ref "J6") (pin "1") (pinfunction "1_1") (pintype "passive"))
      (node (ref "J6") (pin "2") (pinfunction "2_2") (pintype "passive"))
      (node (ref "R1") (pin "1") (pinfunction "1_1") (pintype "passive"))
    )
    (net (code "89") (name "unconnected-(U4-N{slash}C-Pad2)") (class "Default")
      (node (ref "U4") (pin "2") (pinfunction "N/C_2") (pintype "passive"))
    )
    (net (code "90") (name "unconnected-(U4-N{slash}C-Pad5)") (class "Default")
      (node (ref "U4") (pin "5") (pinfunction "N/C_5") (pintype "passive"))
    )
    (net (code "91") (name "unconnected-(U4-N{slash}C-Pad7)") (class "Default")
      (node (ref "U4") (pin "7") (pinfunction "N/C_7") (pintype "passive"))
    )
    (net (code "92") (name "unconnected-(U8-NC-Pad9)") (class "Default")
      (node (ref "U8") (pin "9") (pinfunction "NC_9") (pintype "passive+no_connect"))
    )
    (net (code "93") (name "unconnected-(X2-Pad2)") (class "Default")
      (node (ref "X2") (pin "2") (pinfunction "2_2") (pintype "passive"))
    )
    (net (code "94") (name "unconnected-(X2-Pad3)") (class "Default")
      (node (ref "X2") (pin "3") (pinfunction "3_3") (pintype "passive"))
    )
  )
)
